# FiltroRF.net
KiCad netlist of a schematic drawn in Altium Designer
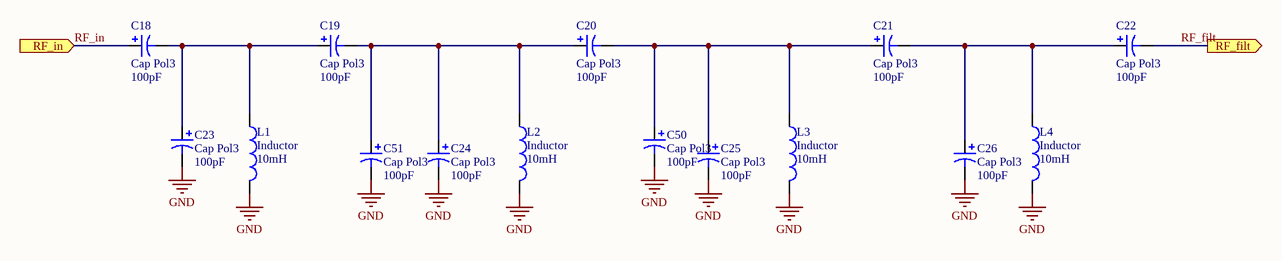
[diagram p0: FiltroRF.SchDoc]

(export (version "E")
  (design (tool "Eeschema 10.0.6"))
  (components
    (comp (ref "C18")
      (value "Cap Pol3")
      (footprint "C0805")
      (description "Polarized Capacitor (Surface Mount)")
      (fields (field (name "ALTIUM_VALUE") "100pF") (field (name "PUBLISHER") "Altium Limited"))
      (libsource (lib "Miscellaneous Devices") (part "Cap Pol3"))
    )
    (comp (ref "C19")
      (value "Cap Pol3")
      (footprint "C0805")
      (description "Polarized Capacitor (Surface Mount)")
      (fields (field (name "ALTIUM_VALUE") "100pF") (field (name "PUBLISHER") "Altium Limited"))
      (libsource (lib "Miscellaneous Devices") (part "Cap Pol3"))
    )
    (comp (ref "C20")
      (value "Cap Pol3")
      (footprint "C0805")
      (description "Polarized Capacitor (Surface Mount)")
      (fields (field (name "ALTIUM_VALUE") "100pF") (field (name "PUBLISHER") "Altium Limited"))
      (libsource (lib "Miscellaneous Devices") (part "Cap Pol3"))
    )
    (comp (ref "C21")
      (value "Cap Pol3")
      (footprint "C0805")
      (description "Polarized Capacitor (Surface Mount)")
      (fields (field (name "ALTIUM_VALUE") "100pF") (field (name "PUBLISHER") "Altium Limited"))
      (libsource (lib "Miscellaneous Devices") (part "Cap Pol3"))
    )
    (comp (ref "C22")
      (value "Cap Pol3")
      (footprint "C0805")
      (description "Polarized Capacitor (Surface Mount)")
      (fields (field (name "ALTIUM_VALUE") "100pF") (field (name "PUBLISHER") "Altium Limited"))
      (libsource (lib "Miscellaneous Devices") (part "Cap Pol3"))
    )
    (comp (ref "C23")
      (value "Cap Pol3")
      (footprint "C0805")
      (description "Polarized Capacitor (Surface Mount)")
      (fields (field (name "ALTIUM_VALUE") "100pF") (field (name "PUBLISHER") "Altium Limited"))
      (libsource (lib "Miscellaneous Devices") (part "Cap Pol3"))
    )
    (comp (ref "C24")
      (value "Cap Pol3")
      (footprint "C0805")
      (description "Polarized Capacitor (Surface Mount)")
      (fields (field (name "ALTIUM_VALUE") "100pF") (field (name "PUBLISHER") "Altium Limited"))
      (libsource (lib "Miscellaneous Devices") (part "Cap Pol3"))
    )
    (comp (ref "C25")
      (value "Cap Pol3")
      (footprint "C0805")
      (description "Polarized Capacitor (Surface Mount)")
      (fields (field (name "ALTIUM_VALUE") "100pF") (field (name "PUBLISHER") "Altium Limited"))
      (libsource (lib "Miscellaneous Devices") (part "Cap Pol3"))
    )
    (comp (ref "C26")
      (value "Cap Pol3")
      (footprint "C0805")
      (description "Polarized Capacitor (Surface Mount)")
      (fields (field (name "ALTIUM_VALUE") "100pF") (field (name "PUBLISHER") "Altium Limited"))
      (libsource (lib "Miscellaneous Devices") (part "Cap Pol3"))
    )
    (comp (ref "C50")
      (value "Cap Pol3")
      (footprint "C0805")
      (description "Polarized Capacitor (Surface Mount)")
      (fields (field (name "ALTIUM_VALUE") "100pF") (field (name "PUBLISHER") "Altium Limited"))
      (libsource (lib "Miscellaneous Devices") (part "Cap Pol3"))
    )
    (comp (ref "C51")
      (value "Cap Pol3")
      (footprint "C0805")
      (description "Polarized Capacitor (Surface Mount)")
      (fields (field (name "ALTIUM_VALUE") "100pF") (field (name "PUBLISHER") "Altium Limited"))
      (libsource (lib "Miscellaneous Devices") (part "Cap Pol3"))
    )
    (comp (ref "L1")
      (value "Inductor")
      (footprint "3261")
      (fields (field (name "ALTIUM_VALUE") "10mH") (field (name "PUBLISHER") "Altium Limited"))
      (libsource (lib "Miscellaneous Devices") (part "Inductor"))
    )
    (comp (ref "L2")
      (value "Inductor")
      (footprint "3261")
      (fields (field (name "ALTIUM_VALUE") "10mH") (field (name "PUBLISHER") "Altium Limited"))
      (libsource (lib "Miscellaneous Devices") (part "Inductor"))
    )
    (comp (ref "L3")
      (value "Inductor")
      (footprint "3261")
      (fields (field (name "ALTIUM_VALUE") "10mH") (field (name "PUBLISHER") "Altium Limited"))
      (libsource (lib "Miscellaneous Devices") (part "Inductor"))
    )
    (comp (ref "L4")
      (value "Inductor")
      (footprint "3261")
      (fields (field (name "ALTIUM_VALUE") "10mH") (field (name "PUBLISHER") "Altium Limited"))
      (libsource (lib "Miscellaneous Devices") (part "Inductor"))
    )
  )
  (nets
    (net (code "1") (name "/RF_filt") (class "Default")
      (node (ref "C22") (pin "2") (pinfunction "2_2") (pintype "passive"))
    )
    (net (code "2") (name "/RF_in") (class "Default")
      (node (ref "C18") (pin "1") (pinfunction "1_1") (pintype "passive"))
    )
    (net (code "3") (name "GND") (class "Default")
      (node (ref "C23") (pin "2") (pinfunction "2_2") (pintype "passive"))
      (node (ref "C24") (pin "2") (pinfunction "2_2") (pintype "passive"))
      (node (ref "C25") (pin "2") (pinfunction "2_2") (pintype "passive"))
      (node (ref "C26") (pin "2") (pinfunction "2_2") (pintype "passive"))
      (node (ref "C50") (pin "2") (pinfunction "2_2") (pintype "passive"))
      (node (ref "C51") (pin "2") (pinfunction "2_2") (pintype "passive"))
      (node (ref "L1") (pin "2") (pinfunction "2_2") (pintype "passive"))
      (node (ref "L2") (pin "2") (pinfunction "2_2") (pintype "passive"))
      (node (ref "L3") (pin "2") (pinfunction "2_2") (pintype "passive"))
      (node (ref "L4") (pin "2") (pinfunction "2_2") (pintype "passive"))
    )
    (net (code "4") (name "Net-(C18-Pad2)") (class "Default")
      (node (ref "C18") (pin "2") (pinfunction "2_2") (pintype "passive"))
      (node (ref "C19") (pin "1") (pinfunction "1_1") (pintype "passive"))
      (node (ref "C23") (pin "1") (pinfunction "1_1") (pintype "passive"))
      (node (ref "L1") (pin "1") (pinfunction "1_1") (pintype "passive"))
    )
    (net (code "5") (name "Net-(C19-Pad2)") (class "Default")
      (node (ref "C19") (pin "2") (pinfunction "2_2") (pintype "passive"))
      (node (ref "C20") (pin "1") (pinfunction "1_1") (pintype "passive"))
      (node (ref "C24") (pin "1") (pinfunction "1_1") (pintype "passive"))
      (node (ref "C51") (pin "1") (pinfunction "1_1") (pintype "passive"))
      (node (ref "L2") (pin "1") (pinfunction "1_1") (pintype "passive"))
    )
    (net (code "6") (name "Net-(C20-Pad2)") (class "Default")
      (node (ref "C20") (pin "2") (pinfunction "2_2") (pintype "passive"))
      (node (ref "C21") (pin "1") (pinfunction "1_1") (pintype "passive"))
      (node (ref "C25") (pin "1") (pinfunction "1_1") (pintype "passive"))
      (node (ref "C50") (pin "1") (pinfunction "1_1") (pintype "passive"))
      (node (ref "L3") (pin "1") (pinfunction "1_1") (pintype "passive"))
    )
    (net (code "7") (name "Net-(C21-Pad2)") (class "Default")
      (node (ref "C21") (pin "2") (pinfunction "2_2") (pintype "passive"))
      (node (ref "C22") (pin "1") (pinfunction "1_1") (pintype "passive"))
      (node (ref "C26") (pin "1") (pinfunction "1_1") (pintype "passive"))
      (node (ref "L4") (pin "1") (pinfunction "1_1") (pintype "passive"))
    )
  )
)
